# Shelly-FTDI.net
KiCad netlist of a schematic drawn in EAGLE
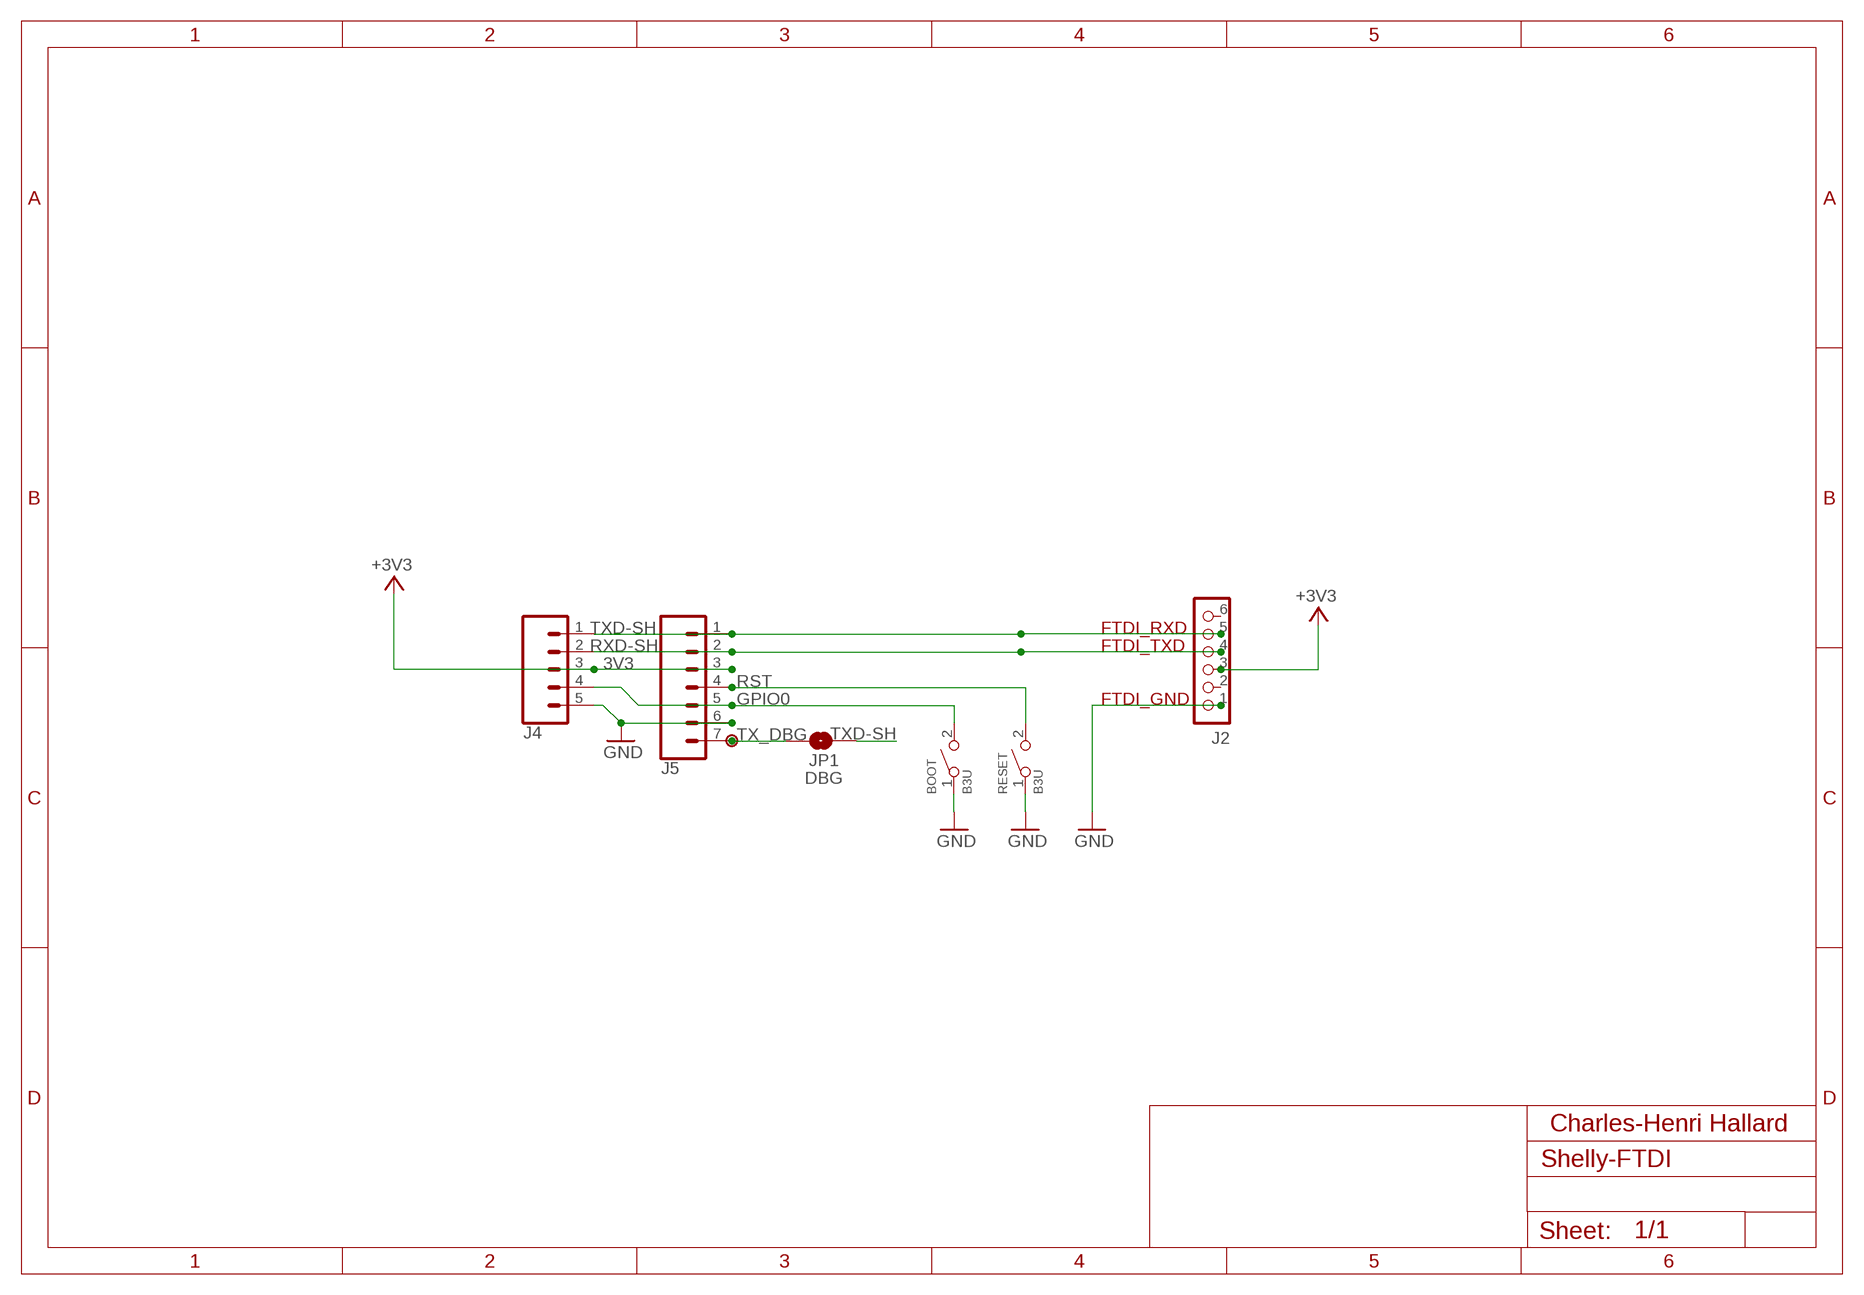
[diagram p0: schematic, sheet 1]

(export (version "E")
  (design (tool "Eeschema 10.0.6"))
  (components
    (comp (ref "BOOT")
      (value "B3U")
      (footprint "eagle-import:SW2-2.6-3.0X2.5X1.2+0.4MM")
      (fields (field (name "MPN") "B3U-1000P-2P-SMD"))
      (libsource (lib "eagle-import") (part "SMD-BUTTON(2P-3.0X2.5X1.2+0.4MM)-B3U-1000P-2P-SMD"))
    )
    (comp (ref "J2")
      (value "CON_HEADER_1X06-PTH")
      (footprint "eagle-import:M1X6")
      (libsource (lib "eagle-import") (part "CON_HEADER_1X06-PTH"))
    )
    (comp (ref "J4")
      (value "CONN_051.27MM")
      (footprint "eagle-import:1X05_1.27MM")
      (libsource (lib "eagle-import") (part "CONN_051.27MM"))
    )
    (comp (ref "J5")
      (value "CONN_071.27")
      (footprint "eagle-import:1X07_1.27MM")
      (libsource (lib "eagle-import") (part "CONN_071.27"))
    )
    (comp (ref "JP1")
      (value "DBG")
      (footprint "eagle-import:PAD-JUMPER-2-NO_NO_SILK")
      (libsource (lib "eagle-import") (part "JUMPER-PAD-2-NO"))
    )
    (comp (ref "P1")
      (value "PADSMALL")
      (footprint "eagle-import:PAD-SMALL")
      (libsource (lib "eagle-import") (part "PADSMALL"))
    )
    (comp (ref "RESET")
      (value "B3U")
      (footprint "eagle-import:SW2-2.6-3.0X2.5X1.2+0.4MM")
      (fields (field (name "MPN") "B3U-1000P-2P-SMD"))
      (libsource (lib "eagle-import") (part "SMD-BUTTON(2P-3.0X2.5X1.2+0.4MM)-B3U-1000P-2P-SMD"))
    )
  )
  (nets
    (net (code "1") (name "+3V3") (class "Default")
      (node (ref "J2") (pin "3") (pinfunction "3_3") (pintype "passive"))
      (node (ref "J4") (pin "3") (pinfunction "3_3") (pintype "passive"))
      (node (ref "J5") (pin "3") (pinfunction "3_3") (pintype "passive"))
    )
    (net (code "2") (name "/GPIO0") (class "Default")
      (node (ref "BOOT") (pin "2") (pinfunction "2_2") (pintype "bidirectional"))
      (node (ref "J4") (pin "4") (pinfunction "4_4") (pintype "passive"))
      (node (ref "J5") (pin "5") (pinfunction "5_5") (pintype "passive"))
    )
    (net (code "3") (name "/RST") (class "Default")
      (node (ref "J5") (pin "4") (pinfunction "4_4") (pintype "passive"))
      (node (ref "RESET") (pin "2") (pinfunction "2_2") (pintype "bidirectional"))
    )
    (net (code "4") (name "/RXD-SH") (class "Default")
      (node (ref "J2") (pin "4") (pinfunction "4_4") (pintype "passive"))
      (node (ref "J4") (pin "2") (pinfunction "2_2") (pintype "passive"))
      (node (ref "J5") (pin "2") (pinfunction "2_2") (pintype "passive"))
    )
    (net (code "5") (name "/TXD-SH") (class "Default")
      (node (ref "J2") (pin "5") (pinfunction "5_5") (pintype "passive"))
      (node (ref "J4") (pin "1") (pinfunction "1_1") (pintype "passive"))
      (node (ref "J5") (pin "1") (pinfunction "1_1") (pintype "passive"))
      (node (ref "JP1") (pin "1") (pinfunction "1_1") (pintype "passive"))
    )
    (net (code "6") (name "/TX_DBG") (class "Default")
      (node (ref "J5") (pin "7") (pinfunction "7_7") (pintype "passive"))
      (node (ref "JP1") (pin "2") (pinfunction "2_2") (pintype "passive"))
      (node (ref "P1") (pin "1") (pinfunction "1_1") (pintype "bidirectional"))
    )
    (net (code "7") (name "GND") (class "Default")
      (node (ref "BOOT") (pin "1") (pinfunction "1_1") (pintype "bidirectional"))
      (node (ref "J2") (pin "1") (pinfunction "1_1") (pintype "bidirectional"))
      (node (ref "J4") (pin "5") (pinfunction "5_5") (pintype "passive"))
      (node (ref "J5") (pin "6") (pinfunction "6_6") (pintype "passive"))
      (node (ref "RESET") (pin "1") (pinfunction "1_1") (pintype "bidirectional"))
    )
    (net (code "8") (name "unconnected-(J2-Pad2)") (class "Default")
      (node (ref "J2") (pin "2") (pinfunction "2_2") (pintype "bidirectional"))
    )
    (net (code "9") (name "unconnected-(J2-Pad6)") (class "Default")
      (node (ref "J2") (pin "6") (pinfunction "6_6") (pintype "passive"))
    )
  )
)
